# io.net
KiCad netlist of a schematic drawn in Altium Designer
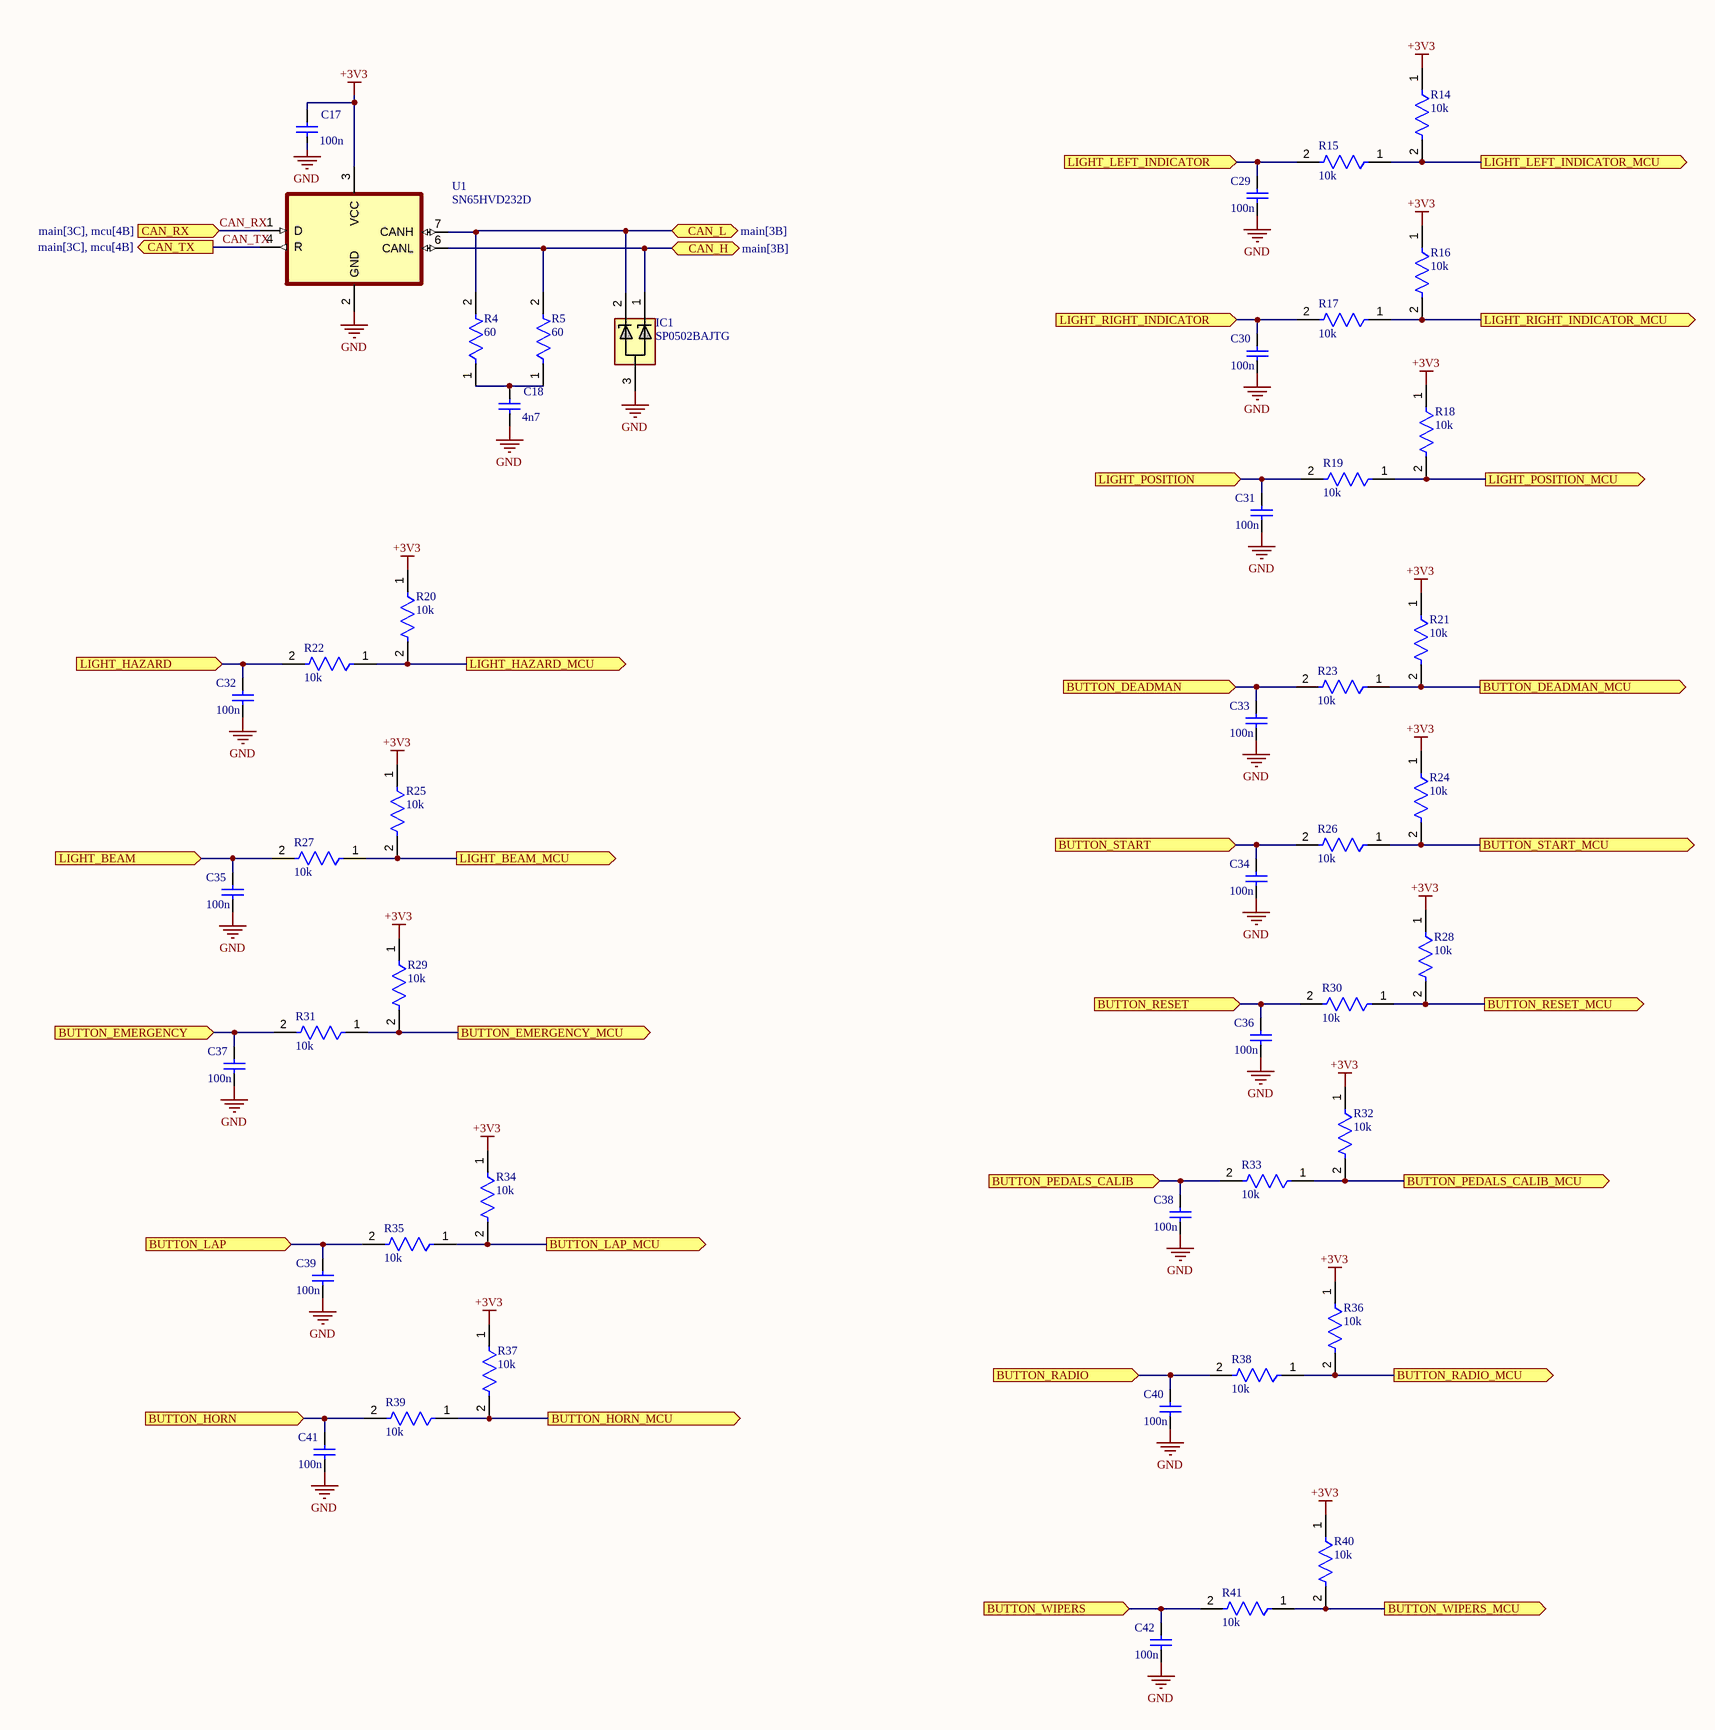
[diagram p0: io.SchDoc]

(export (version "E")
  (design (tool "Eeschema 10.0.6"))
  (components
    (comp (ref "C17")
      (value "100n")
      (footprint "CAPC1206(3216)150_L")
      (description "CAP 1.8uF 10V ±5% 1206 (3216 Metric) Thickness 1.45mm SMD")
      (fields (field (name "TOLERANCE") "Â±5%"))
      (libsource (lib "Altium Content Vault") (part "CAP"))
    )
    (comp (ref "C18")
      (value "4n7")
      (footprint "CAPC1206(3216)150_L")
      (description "CAP 1.8uF 10V ±5% 1206 (3216 Metric) Thickness 1.45mm SMD")
      (fields (field (name "TOLERANCE") "Â±5%"))
      (libsource (lib "Altium Content Vault") (part "CAP"))
    )
    (comp (ref "C29")
      (value "100n")
      (footprint "CAPC1206(3216)150_L")
      (description "CAP 1.8uF 10V ±5% 1206 (3216 Metric) Thickness 1.45mm SMD")
      (fields (field (name "TOLERANCE") "Â±5%"))
      (libsource (lib "Altium Content Vault") (part "CAP"))
    )
    (comp (ref "C30")
      (value "100n")
      (footprint "CAPC1206(3216)150_L")
      (description "CAP 1.8uF 10V ±5% 1206 (3216 Metric) Thickness 1.45mm SMD")
      (fields (field (name "TOLERANCE") "Â±5%"))
      (libsource (lib "Altium Content Vault") (part "CAP"))
    )
    (comp (ref "C31")
      (value "100n")
      (footprint "CAPC1206(3216)150_L")
      (description "CAP 1.8uF 10V ±5% 1206 (3216 Metric) Thickness 1.45mm SMD")
      (fields (field (name "TOLERANCE") "Â±5%"))
      (libsource (lib "Altium Content Vault") (part "CAP"))
    )
    (comp (ref "C32")
      (value "100n")
      (footprint "CAPC1206(3216)150_L")
      (description "CAP 1.8uF 10V ±5% 1206 (3216 Metric) Thickness 1.45mm SMD")
      (fields (field (name "TOLERANCE") "Â±5%"))
      (libsource (lib "Altium Content Vault") (part "CAP"))
    )
    (comp (ref "C33")
      (value "100n")
      (footprint "CAPC1206(3216)150_L")
      (description "CAP 1.8uF 10V ±5% 1206 (3216 Metric) Thickness 1.45mm SMD")
      (fields (field (name "TOLERANCE") "Â±5%"))
      (libsource (lib "Altium Content Vault") (part "CAP"))
    )
    (comp (ref "C34")
      (value "100n")
      (footprint "CAPC1206(3216)150_L")
      (description "CAP 1.8uF 10V ±5% 1206 (3216 Metric) Thickness 1.45mm SMD")
      (fields (field (name "TOLERANCE") "Â±5%"))
      (libsource (lib "Altium Content Vault") (part "CAP"))
    )
    (comp (ref "C35")
      (value "100n")
      (footprint "CAPC1206(3216)150_L")
      (description "CAP 1.8uF 10V ±5% 1206 (3216 Metric) Thickness 1.45mm SMD")
      (fields (field (name "TOLERANCE") "Â±5%"))
      (libsource (lib "Altium Content Vault") (part "CAP"))
    )
    (comp (ref "C36")
      (value "100n")
      (footprint "CAPC1206(3216)150_L")
      (description "CAP 1.8uF 10V ±5% 1206 (3216 Metric) Thickness 1.45mm SMD")
      (fields (field (name "TOLERANCE") "Â±5%"))
      (libsource (lib "Altium Content Vault") (part "CAP"))
    )
    (comp (ref "C37")
      (value "100n")
      (footprint "CAPC1206(3216)150_L")
      (description "CAP 1.8uF 10V ±5% 1206 (3216 Metric) Thickness 1.45mm SMD")
      (fields (field (name "TOLERANCE") "Â±5%"))
      (libsource (lib "Altium Content Vault") (part "CAP"))
    )
    (comp (ref "C38")
      (value "100n")
      (footprint "CAPC1206(3216)150_L")
      (description "CAP 1.8uF 10V ±5% 1206 (3216 Metric) Thickness 1.45mm SMD")
      (fields (field (name "TOLERANCE") "Â±5%"))
      (libsource (lib "Altium Content Vault") (part "CAP"))
    )
    (comp (ref "C39")
      (value "100n")
      (footprint "CAPC1206(3216)150_L")
      (description "CAP 1.8uF 10V ±5% 1206 (3216 Metric) Thickness 1.45mm SMD")
      (fields (field (name "TOLERANCE") "Â±5%"))
      (libsource (lib "Altium Content Vault") (part "CAP"))
    )
    (comp (ref "C40")
      (value "100n")
      (footprint "CAPC1206(3216)150_L")
      (description "CAP 1.8uF 10V ±5% 1206 (3216 Metric) Thickness 1.45mm SMD")
      (fields (field (name "TOLERANCE") "Â±5%"))
      (libsource (lib "Altium Content Vault") (part "CAP"))
    )
    (comp (ref "C41")
      (value "100n")
      (footprint "CAPC1206(3216)150_L")
      (description "CAP 1.8uF 10V ±5% 1206 (3216 Metric) Thickness 1.45mm SMD")
      (fields (field (name "TOLERANCE") "Â±5%"))
      (libsource (lib "Altium Content Vault") (part "CAP"))
    )
    (comp (ref "C42")
      (value "100n")
      (footprint "CAPC1206(3216)150_L")
      (description "CAP 1.8uF 10V ±5% 1206 (3216 Metric) Thickness 1.45mm SMD")
      (fields (field (name "TOLERANCE") "Â±5%"))
      (libsource (lib "Altium Content Vault") (part "CAP"))
    )
    (comp (ref "IC1")
      (value "SP0502BAJTG")
      (footprint "SOT132P220X110-3N")
      (description "Integrated Circuit")
      (fields (field (name "MOUSER PART NUMBER") "576-SP0502BAJTG"))
      (libsource (lib "HydrogreenLibrary") (part "SP0502BAJTG"))
    )
    (comp (ref "R4")
      (value "60")
      (footprint "FP-RK73H2B-MFG")
      (description "40.2kΩ ±1% 0.25W Chip Resistor 1206 Thick Film AEC-Q200 Qualified")
      (fields (field (name "TOLERANCE") "1%"))
      (libsource (lib "Altium Content Vault") (part "1029c3af85768c4190bb7ad29bc67b5"))
    )
    (comp (ref "R5")
      (value "60")
      (footprint "FP-RK73H2B-MFG")
      (description "40.2kΩ ±1% 0.25W Chip Resistor 1206 Thick Film AEC-Q200 Qualified")
      (fields (field (name "TOLERANCE") "1%"))
      (libsource (lib "Altium Content Vault") (part "1029c3af85768c4190bb7ad29bc67b5"))
    )
    (comp (ref "R14")
      (value "10k")
      (footprint "FP-RK73H2B-MFG")
      (description "40.2kΩ ±1% 0.25W Chip Resistor 1206 Thick Film AEC-Q200 Qualified")
      (fields (field (name "TOLERANCE") "1%"))
      (libsource (lib "Altium Content Vault") (part "1029c3af85768c4190bb7ad29bc67b5"))
    )
    (comp (ref "R15")
      (value "10k")
      (footprint "FP-RK73H2B-MFG")
      (description "40.2kΩ ±1% 0.25W Chip Resistor 1206 Thick Film AEC-Q200 Qualified")
      (fields (field (name "TOLERANCE") "1%"))
      (libsource (lib "Altium Content Vault") (part "1029c3af85768c4190bb7ad29bc67b5"))
    )
    (comp (ref "R16")
      (value "10k")
      (footprint "FP-RK73H2B-MFG")
      (description "40.2kΩ ±1% 0.25W Chip Resistor 1206 Thick Film AEC-Q200 Qualified")
      (fields (field (name "TOLERANCE") "1%"))
      (libsource (lib "Altium Content Vault") (part "1029c3af85768c4190bb7ad29bc67b5"))
    )
    (comp (ref "R17")
      (value "10k")
      (footprint "FP-RK73H2B-MFG")
      (description "40.2kΩ ±1% 0.25W Chip Resistor 1206 Thick Film AEC-Q200 Qualified")
      (fields (field (name "TOLERANCE") "1%"))
      (libsource (lib "Altium Content Vault") (part "1029c3af85768c4190bb7ad29bc67b5"))
    )
    (comp (ref "R18")
      (value "10k")
      (footprint "FP-RK73H2B-MFG")
      (description "40.2kΩ ±1% 0.25W Chip Resistor 1206 Thick Film AEC-Q200 Qualified")
      (fields (field (name "TOLERANCE") "1%"))
      (libsource (lib "Altium Content Vault") (part "1029c3af85768c4190bb7ad29bc67b5"))
    )
    (comp (ref "R19")
      (value "10k")
      (footprint "FP-RK73H2B-MFG")
      (description "40.2kΩ ±1% 0.25W Chip Resistor 1206 Thick Film AEC-Q200 Qualified")
      (fields (field (name "TOLERANCE") "1%"))
      (libsource (lib "Altium Content Vault") (part "1029c3af85768c4190bb7ad29bc67b5"))
    )
    (comp (ref "R20")
      (value "10k")
      (footprint "FP-RK73H2B-MFG")
      (description "40.2kΩ ±1% 0.25W Chip Resistor 1206 Thick Film AEC-Q200 Qualified")
      (fields (field (name "TOLERANCE") "1%"))
      (libsource (lib "Altium Content Vault") (part "1029c3af85768c4190bb7ad29bc67b5"))
    )
    (comp (ref "R21")
      (value "10k")
      (footprint "FP-RK73H2B-MFG")
      (description "40.2kΩ ±1% 0.25W Chip Resistor 1206 Thick Film AEC-Q200 Qualified")
      (fields (field (name "TOLERANCE") "1%"))
      (libsource (lib "Altium Content Vault") (part "1029c3af85768c4190bb7ad29bc67b5"))
    )
    (comp (ref "R22")
      (value "10k")
      (footprint "FP-RK73H2B-MFG")
      (description "40.2kΩ ±1% 0.25W Chip Resistor 1206 Thick Film AEC-Q200 Qualified")
      (fields (field (name "TOLERANCE") "1%"))
      (libsource (lib "Altium Content Vault") (part "1029c3af85768c4190bb7ad29bc67b5"))
    )
    (comp (ref "R23")
      (value "10k")
      (footprint "FP-RK73H2B-MFG")
      (description "40.2kΩ ±1% 0.25W Chip Resistor 1206 Thick Film AEC-Q200 Qualified")
      (fields (field (name "TOLERANCE") "1%"))
      (libsource (lib "Altium Content Vault") (part "1029c3af85768c4190bb7ad29bc67b5"))
    )
    (comp (ref "R24")
      (value "10k")
      (footprint "FP-RK73H2B-MFG")
      (description "40.2kΩ ±1% 0.25W Chip Resistor 1206 Thick Film AEC-Q200 Qualified")
      (fields (field (name "TOLERANCE") "1%"))
      (libsource (lib "Altium Content Vault") (part "1029c3af85768c4190bb7ad29bc67b5"))
    )
    (comp (ref "R25")
      (value "10k")
      (footprint "FP-RK73H2B-MFG")
      (description "40.2kΩ ±1% 0.25W Chip Resistor 1206 Thick Film AEC-Q200 Qualified")
      (fields (field (name "TOLERANCE") "1%"))
      (libsource (lib "Altium Content Vault") (part "1029c3af85768c4190bb7ad29bc67b5"))
    )
    (comp (ref "R26")
      (value "10k")
      (footprint "FP-RK73H2B-MFG")
      (description "40.2kΩ ±1% 0.25W Chip Resistor 1206 Thick Film AEC-Q200 Qualified")
      (fields (field (name "TOLERANCE") "1%"))
      (libsource (lib "Altium Content Vault") (part "1029c3af85768c4190bb7ad29bc67b5"))
    )
    (comp (ref "R27")
      (value "10k")
      (footprint "FP-RK73H2B-MFG")
      (description "40.2kΩ ±1% 0.25W Chip Resistor 1206 Thick Film AEC-Q200 Qualified")
      (fields (field (name "TOLERANCE") "1%"))
      (libsource (lib "Altium Content Vault") (part "1029c3af85768c4190bb7ad29bc67b5"))
    )
    (comp (ref "R28")
      (value "10k")
      (footprint "FP-RK73H2B-MFG")
      (description "40.2kΩ ±1% 0.25W Chip Resistor 1206 Thick Film AEC-Q200 Qualified")
      (fields (field (name "TOLERANCE") "1%"))
      (libsource (lib "Altium Content Vault") (part "1029c3af85768c4190bb7ad29bc67b5"))
    )
    (comp (ref "R29")
      (value "10k")
      (footprint "FP-RK73H2B-MFG")
      (description "40.2kΩ ±1% 0.25W Chip Resistor 1206 Thick Film AEC-Q200 Qualified")
      (fields (field (name "TOLERANCE") "1%"))
      (libsource (lib "Altium Content Vault") (part "1029c3af85768c4190bb7ad29bc67b5"))
    )
    (comp (ref "R30")
      (value "10k")
      (footprint "FP-RK73H2B-MFG")
      (description "40.2kΩ ±1% 0.25W Chip Resistor 1206 Thick Film AEC-Q200 Qualified")
      (fields (field (name "TOLERANCE") "1%"))
      (libsource (lib "Altium Content Vault") (part "1029c3af85768c4190bb7ad29bc67b5"))
    )
    (comp (ref "R31")
      (value "10k")
      (footprint "FP-RK73H2B-MFG")
      (description "40.2kΩ ±1% 0.25W Chip Resistor 1206 Thick Film AEC-Q200 Qualified")
      (fields (field (name "TOLERANCE") "1%"))
      (libsource (lib "Altium Content Vault") (part "1029c3af85768c4190bb7ad29bc67b5"))
    )
    (comp (ref "R32")
      (value "10k")
      (footprint "FP-RK73H2B-MFG")
      (description "40.2kΩ ±1% 0.25W Chip Resistor 1206 Thick Film AEC-Q200 Qualified")
      (fields (field (name "TOLERANCE") "1%"))
      (libsource (lib "Altium Content Vault") (part "1029c3af85768c4190bb7ad29bc67b5"))
    )
    (comp (ref "R33")
      (value "10k")
      (footprint "FP-RK73H2B-MFG")
      (description "40.2kΩ ±1% 0.25W Chip Resistor 1206 Thick Film AEC-Q200 Qualified")
      (fields (field (name "TOLERANCE") "1%"))
      (libsource (lib "Altium Content Vault") (part "1029c3af85768c4190bb7ad29bc67b5"))
    )
    (comp (ref "R34")
      (value "10k")
      (footprint "FP-RK73H2B-MFG")
      (description "40.2kΩ ±1% 0.25W Chip Resistor 1206 Thick Film AEC-Q200 Qualified")
      (fields (field (name "TOLERANCE") "1%"))
      (libsource (lib "Altium Content Vault") (part "1029c3af85768c4190bb7ad29bc67b5"))
    )
    (comp (ref "R35")
      (value "10k")
      (footprint "FP-RK73H2B-MFG")
      (description "40.2kΩ ±1% 0.25W Chip Resistor 1206 Thick Film AEC-Q200 Qualified")
      (fields (field (name "TOLERANCE") "1%"))
      (libsource (lib "Altium Content Vault") (part "1029c3af85768c4190bb7ad29bc67b5"))
    )
    (comp (ref "R36")
      (value "10k")
      (footprint "FP-RK73H2B-MFG")
      (description "40.2kΩ ±1% 0.25W Chip Resistor 1206 Thick Film AEC-Q200 Qualified")
      (fields (field (name "TOLERANCE") "1%"))
      (libsource (lib "Altium Content Vault") (part "1029c3af85768c4190bb7ad29bc67b5"))
    )
    (comp (ref "R37")
      (value "10k")
      (footprint "FP-RK73H2B-MFG")
      (description "40.2kΩ ±1% 0.25W Chip Resistor 1206 Thick Film AEC-Q200 Qualified")
      (fields (field (name "TOLERANCE") "1%"))
      (libsource (lib "Altium Content Vault") (part "1029c3af85768c4190bb7ad29bc67b5"))
    )
    (comp (ref "R38")
      (value "10k")
      (footprint "FP-RK73H2B-MFG")
      (description "40.2kΩ ±1% 0.25W Chip Resistor 1206 Thick Film AEC-Q200 Qualified")
      (fields (field (name "TOLERANCE") "1%"))
      (libsource (lib "Altium Content Vault") (part "1029c3af85768c4190bb7ad29bc67b5"))
    )
    (comp (ref "R39")
      (value "10k")
      (footprint "FP-RK73H2B-MFG")
      (description "40.2kΩ ±1% 0.25W Chip Resistor 1206 Thick Film AEC-Q200 Qualified")
      (fields (field (name "TOLERANCE") "1%"))
      (libsource (lib "Altium Content Vault") (part "1029c3af85768c4190bb7ad29bc67b5"))
    )
    (comp (ref "R40")
      (value "10k")
      (footprint "FP-RK73H2B-MFG")
      (description "40.2kΩ ±1% 0.25W Chip Resistor 1206 Thick Film AEC-Q200 Qualified")
      (fields (field (name "TOLERANCE") "1%"))
      (libsource (lib "Altium Content Vault") (part "1029c3af85768c4190bb7ad29bc67b5"))
    )
    (comp (ref "R41")
      (value "10k")
      (footprint "FP-RK73H2B-MFG")
      (description "40.2kΩ ±1% 0.25W Chip Resistor 1206 Thick Film AEC-Q200 Qualified")
      (fields (field (name "TOLERANCE") "1%"))
      (libsource (lib "Altium Content Vault") (part "1029c3af85768c4190bb7ad29bc67b5"))
    )
    (comp (ref "U1")
      (value "SN65HVD232D")
      (footprint "SN65HVD232D")
      (description "Texas Instruments - SN65HVD232DR - Can Transceiver, 1MBPS, 1/1, 3.3V, SOIC-8, Full Reel")
      (fields
        (field (name "MF") "Texas Instruments")
        (field (name "MANUFACTURER PART NUMBER") "SN65HVD232DR")
      )
      (libsource (lib "HydrogreenLibrary") (part "SN65HVD232D"))
    )
  )
  (nets
    (net (code "1") (name "+3V3") (class "Default")
      (node (ref "C17") (pin "1") (pinfunction "1_1") (pintype "passive"))
      (node (ref "R14") (pin "1") (pinfunction "1_1") (pintype "passive"))
      (node (ref "R16") (pin "1") (pinfunction "1_1") (pintype "passive"))
      (node (ref "R18") (pin "1") (pinfunction "1_1") (pintype "passive"))
      (node (ref "R20") (pin "1") (pinfunction "1_1") (pintype "passive"))
      (node (ref "R21") (pin "1") (pinfunction "1_1") (pintype "passive"))
      (node (ref "R24") (pin "1") (pinfunction "1_1") (pintype "passive"))
      (node (ref "R25") (pin "1") (pinfunction "1_1") (pintype "passive"))
      (node (ref "R28") (pin "1") (pinfunction "1_1") (pintype "passive"))
      (node (ref "R29") (pin "1") (pinfunction "1_1") (pintype "passive"))
      (node (ref "R32") (pin "1") (pinfunction "1_1") (pintype "passive"))
      (node (ref "R34") (pin "1") (pinfunction "1_1") (pintype "passive"))
      (node (ref "R36") (pin "1") (pinfunction "1_1") (pintype "passive"))
      (node (ref "R37") (pin "1") (pinfunction "1_1") (pintype "passive"))
      (node (ref "R40") (pin "1") (pinfunction "1_1") (pintype "passive"))
      (node (ref "U1") (pin "3") (pinfunction "VCC_3") (pintype "power_in"))
    )
    (net (code "2") (name "/BUTTON_DEADMAN") (class "Default")
      (node (ref "C33") (pin "1") (pinfunction "1_1") (pintype "passive"))
      (node (ref "R23") (pin "2") (pinfunction "2_2") (pintype "passive"))
    )
    (net (code "3") (name "/BUTTON_DEADMAN_MCU") (class "Default")
      (node (ref "R21") (pin "2") (pinfunction "2_2") (pintype "passive"))
      (node (ref "R23") (pin "1") (pinfunction "1_1") (pintype "passive"))
    )
    (net (code "4") (name "/BUTTON_EMERGENCY") (class "Default")
      (node (ref "C37") (pin "1") (pinfunction "1_1") (pintype "passive"))
      (node (ref "R31") (pin "2") (pinfunction "2_2") (pintype "passive"))
    )
    (net (code "5") (name "/BUTTON_EMERGENCY_MCU") (class "Default")
      (node (ref "R29") (pin "2") (pinfunction "2_2") (pintype "passive"))
      (node (ref "R31") (pin "1") (pinfunction "1_1") (pintype "passive"))
    )
    (net (code "6") (name "/BUTTON_HORN") (class "Default")
      (node (ref "C41") (pin "1") (pinfunction "1_1") (pintype "passive"))
      (node (ref "R39") (pin "2") (pinfunction "2_2") (pintype "passive"))
    )
    (net (code "7") (name "/BUTTON_HORN_MCU") (class "Default")
      (node (ref "R37") (pin "2") (pinfunction "2_2") (pintype "passive"))
      (node (ref "R39") (pin "1") (pinfunction "1_1") (pintype "passive"))
    )
    (net (code "8") (name "/BUTTON_LAP") (class "Default")
      (node (ref "C39") (pin "1") (pinfunction "1_1") (pintype "passive"))
      (node (ref "R35") (pin "2") (pinfunction "2_2") (pintype "passive"))
    )
    (net (code "9") (name "/BUTTON_LAP_MCU") (class "Default")
      (node (ref "R34") (pin "2") (pinfunction "2_2") (pintype "passive"))
      (node (ref "R35") (pin "1") (pinfunction "1_1") (pintype "passive"))
    )
    (net (code "10") (name "/BUTTON_PEDALS_CALIB") (class "Default")
      (node (ref "C38") (pin "1") (pinfunction "1_1") (pintype "passive"))
      (node (ref "R33") (pin "2") (pinfunction "2_2") (pintype "passive"))
    )
    (net (code "11") (name "/BUTTON_PEDALS_CALIB_MCU") (class "Default")
      (node (ref "R32") (pin "2") (pinfunction "2_2") (pintype "passive"))
      (node (ref "R33") (pin "1") (pinfunction "1_1") (pintype "passive"))
    )
    (net (code "12") (name "/BUTTON_RADIO") (class "Default")
      (node (ref "C40") (pin "1") (pinfunction "1_1") (pintype "passive"))
      (node (ref "R38") (pin "2") (pinfunction "2_2") (pintype "passive"))
    )
    (net (code "13") (name "/BUTTON_RADIO_MCU") (class "Default")
      (node (ref "R36") (pin "2") (pinfunction "2_2") (pintype "passive"))
      (node (ref "R38") (pin "1") (pinfunction "1_1") (pintype "passive"))
    )
    (net (code "14") (name "/BUTTON_RESET") (class "Default")
      (node (ref "C36") (pin "1") (pinfunction "1_1") (pintype "passive"))
      (node (ref "R30") (pin "2") (pinfunction "2_2") (pintype "passive"))
    )
    (net (code "15") (name "/BUTTON_RESET_MCU") (class "Default")
      (node (ref "R28") (pin "2") (pinfunction "2_2") (pintype "passive"))
      (node (ref "R30") (pin "1") (pinfunction "1_1") (pintype "passive"))
    )
    (net (code "16") (name "/BUTTON_START") (class "Default")
      (node (ref "C34") (pin "1") (pinfunction "1_1") (pintype "passive"))
      (node (ref "R26") (pin "2") (pinfunction "2_2") (pintype "passive"))
    )
    (net (code "17") (name "/BUTTON_START_MCU") (class "Default")
      (node (ref "R24") (pin "2") (pinfunction "2_2") (pintype "passive"))
      (node (ref "R26") (pin "1") (pinfunction "1_1") (pintype "passive"))
    )
    (net (code "18") (name "/BUTTON_WIPERS") (class "Default")
      (node (ref "C42") (pin "1") (pinfunction "1_1") (pintype "passive"))
      (node (ref "R41") (pin "2") (pinfunction "2_2") (pintype "passive"))
    )
    (net (code "19") (name "/BUTTON_WIPERS_MCU") (class "Default")
      (node (ref "R40") (pin "2") (pinfunction "2_2") (pintype "passive"))
      (node (ref "R41") (pin "1") (pinfunction "1_1") (pintype "passive"))
    )
    (net (code "20") (name "/CAN_H") (class "Default")
      (node (ref "IC1") (pin "1") (pintype "passive"))
      (node (ref "R5") (pin "2") (pinfunction "2_2") (pintype "passive"))
      (node (ref "U1") (pin "6") (pinfunction "CANL_6") (pintype "bidirectional"))
    )
    (net (code "21") (name "/CAN_L") (class "Default")
      (node (ref "IC1") (pin "2") (pintype "passive"))
      (node (ref "R4") (pin "2") (pinfunction "2_2") (pintype "passive"))
      (node (ref "U1") (pin "7") (pinfunction "CANH_7") (pintype "bidirectional"))
    )
    (net (code "22") (name "/CAN_RX") (class "Default")
      (node (ref "U1") (pin "1") (pinfunction "D_1") (pintype "input"))
    )
    (net (code "23") (name "/CAN_TX") (class "Default")
      (node (ref "U1") (pin "4") (pinfunction "R_4") (pintype "output"))
    )
    (net (code "24") (name "/LIGHT_BEAM") (class "Default")
      (node (ref "C35") (pin "1") (pinfunction "1_1") (pintype "passive"))
      (node (ref "R27") (pin "2") (pinfunction "2_2") (pintype "passive"))
    )
    (net (code "25") (name "/LIGHT_BEAM_MCU") (class "Default")
      (node (ref "R25") (pin "2") (pinfunction "2_2") (pintype "passive"))
      (node (ref "R27") (pin "1") (pinfunction "1_1") (pintype "passive"))
    )
    (net (code "26") (name "/LIGHT_HAZARD") (class "Default")
      (node (ref "C32") (pin "1") (pinfunction "1_1") (pintype "passive"))
      (node (ref "R22") (pin "2") (pinfunction "2_2") (pintype "passive"))
    )
    (net (code "27") (name "/LIGHT_HAZARD_MCU") (class "Default")
      (node (ref "R20") (pin "2") (pinfunction "2_2") (pintype "passive"))
      (node (ref "R22") (pin "1") (pinfunction "1_1") (pintype "passive"))
    )
    (net (code "28") (name "/LIGHT_LEFT_INDICATOR") (class "Default")
      (node (ref "C29") (pin "1") (pinfunction "1_1") (pintype "passive"))
      (node (ref "R15") (pin "2") (pinfunction "2_2") (pintype "passive"))
    )
    (net (code "29") (name "/LIGHT_LEFT_INDICATOR_MCU") (class "Default")
      (node (ref "R14") (pin "2") (pinfunction "2_2") (pintype "passive"))
      (node (ref "R15") (pin "1") (pinfunction "1_1") (pintype "passive"))
    )
    (net (code "30") (name "/LIGHT_POSITION") (class "Default")
      (node (ref "C31") (pin "1") (pinfunction "1_1") (pintype "passive"))
      (node (ref "R19") (pin "2") (pinfunction "2_2") (pintype "passive"))
    )
    (net (code "31") (name "/LIGHT_POSITION_MCU") (class "Default")
      (node (ref "R18") (pin "2") (pinfunction "2_2") (pintype "passive"))
      (node (ref "R19") (pin "1") (pinfunction "1_1") (pintype "passive"))
    )
    (net (code "32") (name "/LIGHT_RIGHT_INDICATOR") (class "Default")
      (node (ref "C30") (pin "1") (pinfunction "1_1") (pintype "passive"))
      (node (ref "R17") (pin "2") (pinfunction "2_2") (pintype "passive"))
    )
    (net (code "33") (name "/LIGHT_RIGHT_INDICATOR_MCU") (class "Default")
      (node (ref "R16") (pin "2") (pinfunction "2_2") (pintype "passive"))
      (node (ref "R17") (pin "1") (pinfunction "1_1") (pintype "passive"))
    )
    (net (code "34") (name "GND") (class "Default")
      (node (ref "C17") (pin "2") (pinfunction "2_2") (pintype "passive"))
      (node (ref "C18") (pin "2") (pinfunction "2_2") (pintype "passive"))
      (node (ref "C29") (pin "2") (pinfunction "2_2") (pintype "passive"))
      (node (ref "C30") (pin "2") (pinfunction "2_2") (pintype "passive"))
      (node (ref "C31") (pin "2") (pinfunction "2_2") (pintype "passive"))
      (node (ref "C32") (pin "2") (pinfunction "2_2") (pintype "passive"))
      (node (ref "C33") (pin "2") (pinfunction "2_2") (pintype "passive"))
      (node (ref "C34") (pin "2") (pinfunction "2_2") (pintype "passive"))
      (node (ref "C35") (pin "2") (pinfunction "2_2") (pintype "passive"))
      (node (ref "C36") (pin "2") (pinfunction "2_2") (pintype "passive"))
      (node (ref "C37") (pin "2") (pinfunction "2_2") (pintype "passive"))
      (node (ref "C38") (pin "2") (pinfunction "2_2") (pintype "passive"))
      (node (ref "C39") (pin "2") (pinfunction "2_2") (pintype "passive"))
      (node (ref "C40") (pin "2") (pinfunction "2_2") (pintype "passive"))
      (node (ref "C41") (pin "2") (pinfunction "2_2") (pintype "passive"))
      (node (ref "C42") (pin "2") (pinfunction "2_2") (pintype "passive"))
      (node (ref "IC1") (pin "3") (pintype "passive"))
      (node (ref "U1") (pin "2") (pinfunction "GND_2") (pintype "power_in"))
    )
    (net (code "35") (name "Net-(C18-Pad1)") (class "Default")
      (node (ref "C18") (pin "1") (pinfunction "1_1") (pintype "passive"))
      (node (ref "R4") (pin "1") (pinfunction "1_1") (pintype "passive"))
      (node (ref "R5") (pin "1") (pinfunction "1_1") (pintype "passive"))
    )
  )
)
